# W602A.net
KiCad netlist of a schematic drawn in EAGLE
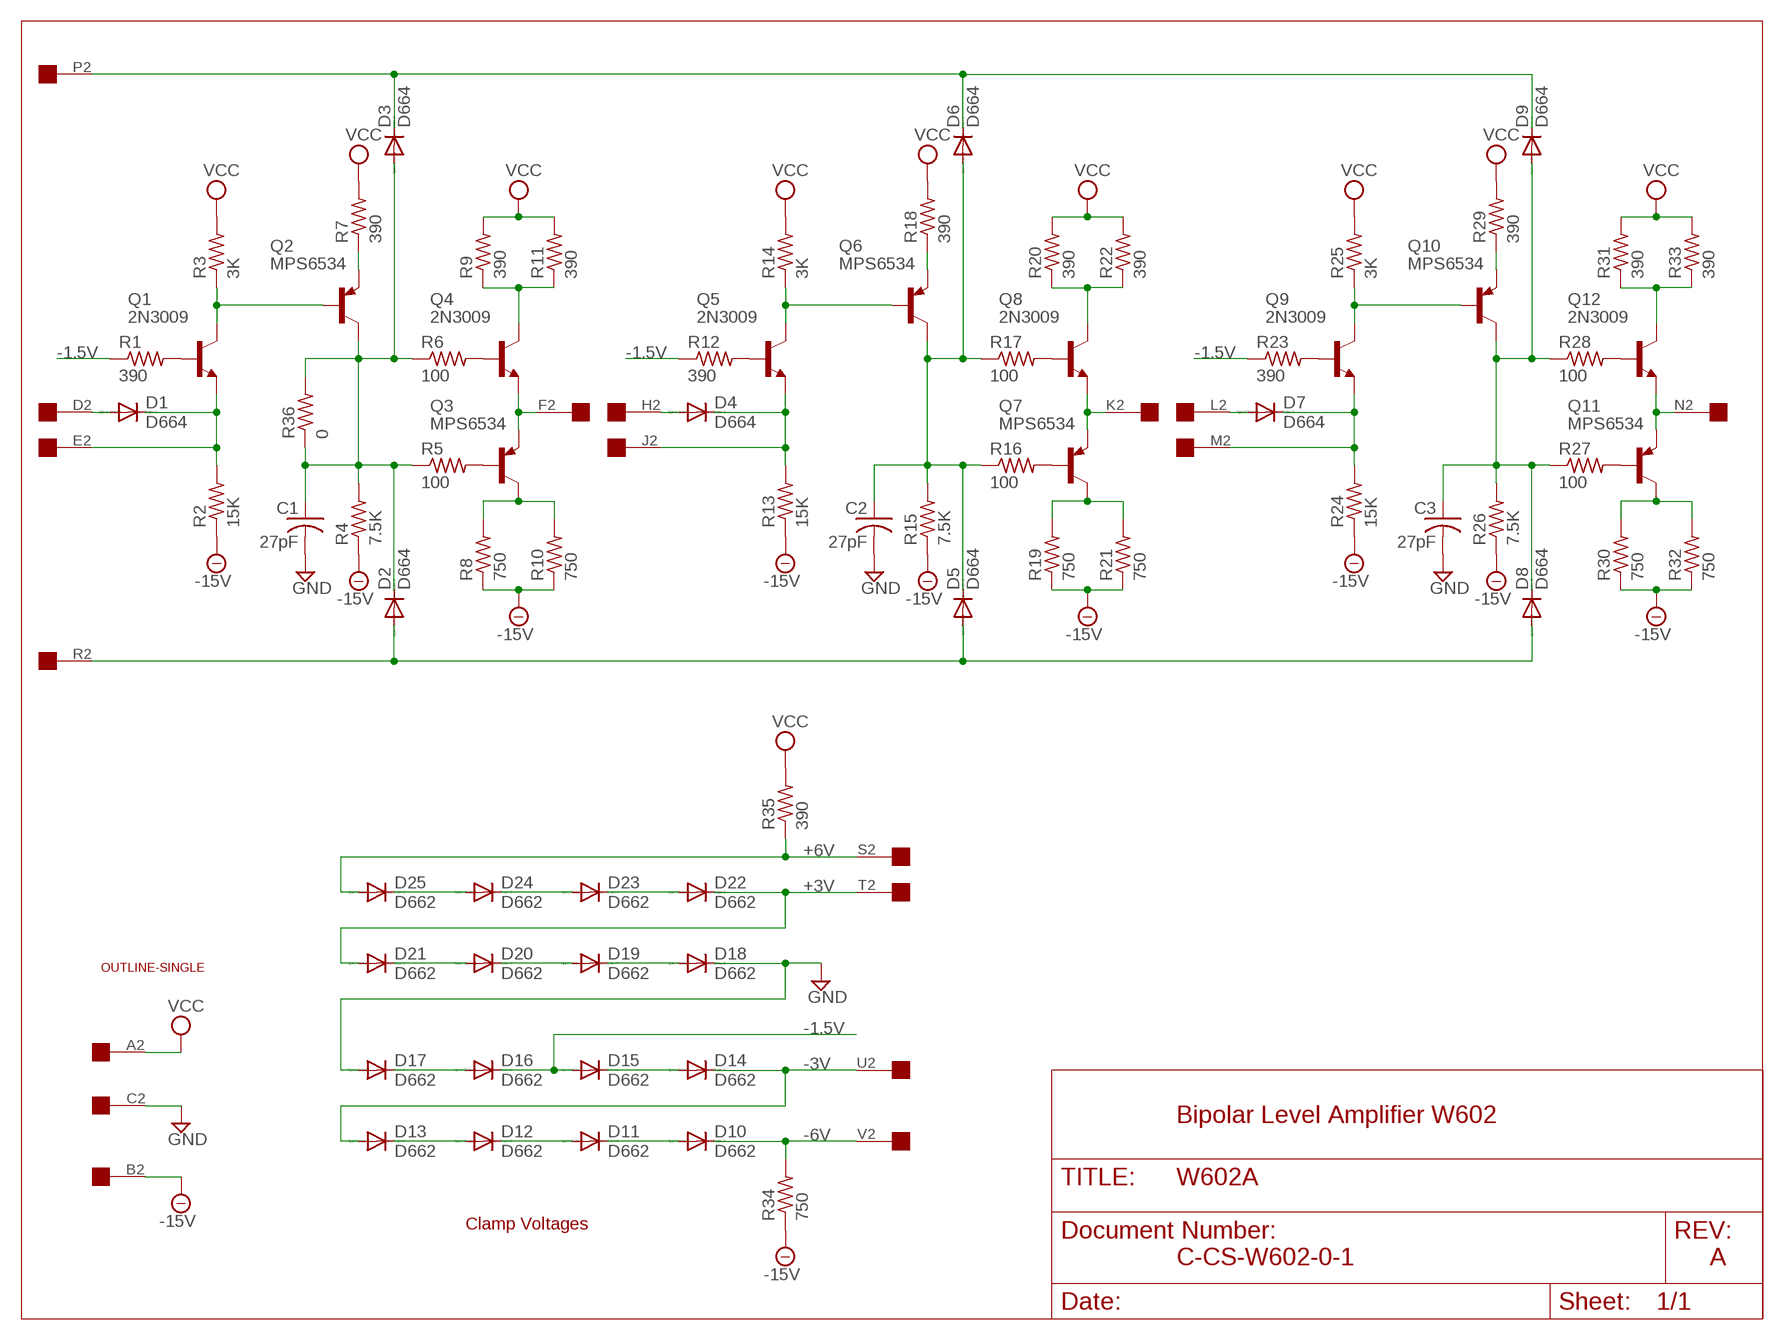
[diagram p0: schematic, sheet 1]

(export (version "E")
  (design (tool "Eeschema 10.0.6"))
  (components
    (comp (ref "C1")
      (value "27pF")
      (footprint "eagle-import:C063-025X075")
      (libsource (lib "eagle-import") (part "C-US"))
    )
    (comp (ref "C2")
      (value "27pF")
      (footprint "eagle-import:C063-025X075")
      (libsource (lib "eagle-import") (part "C-US"))
    )
    (comp (ref "C3")
      (value "27pF")
      (footprint "eagle-import:C063-025X075")
      (libsource (lib "eagle-import") (part "C-US"))
    )
    (comp (ref "D1")
      (value "D664")
      (footprint "eagle-import:DO35-10")
      (libsource (lib "eagle-import") (part "DIODE-DO35-10"))
    )
    (comp (ref "D2")
      (value "D664")
      (footprint "eagle-import:DO35-10")
      (libsource (lib "eagle-import") (part "DIODE-DO35-10"))
    )
    (comp (ref "D3")
      (value "D664")
      (footprint "eagle-import:DO35-10")
      (libsource (lib "eagle-import") (part "DIODE-DO35-10"))
    )
    (comp (ref "D4")
      (value "D664")
      (footprint "eagle-import:DO35-10")
      (libsource (lib "eagle-import") (part "DIODE-DO35-10"))
    )
    (comp (ref "D5")
      (value "D664")
      (footprint "eagle-import:DO35-10")
      (libsource (lib "eagle-import") (part "DIODE-DO35-10"))
    )
    (comp (ref "D6")
      (value "D664")
      (footprint "eagle-import:DO35-10")
      (libsource (lib "eagle-import") (part "DIODE-DO35-10"))
    )
    (comp (ref "D7")
      (value "D664")
      (footprint "eagle-import:DO35-10")
      (libsource (lib "eagle-import") (part "DIODE-DO35-10"))
    )
    (comp (ref "D8")
      (value "D664")
      (footprint "eagle-import:DO35-10")
      (libsource (lib "eagle-import") (part "DIODE-DO35-10"))
    )
    (comp (ref "D9")
      (value "D664")
      (footprint "eagle-import:DO35-10")
      (libsource (lib "eagle-import") (part "DIODE-DO35-10"))
    )
    (comp (ref "D10")
      (value "D662")
      (footprint "eagle-import:DO35-10")
      (libsource (lib "eagle-import") (part "DIODE-DO35-10"))
    )
    (comp (ref "D11")
      (value "D662")
      (footprint "eagle-import:DO35-10")
      (libsource (lib "eagle-import") (part "DIODE-DO35-10"))
    )
    (comp (ref "D12")
      (value "D662")
      (footprint "eagle-import:DO35-10")
      (libsource (lib "eagle-import") (part "DIODE-DO35-10"))
    )
    (comp (ref "D13")
      (value "D662")
      (footprint "eagle-import:DO35-10")
      (libsource (lib "eagle-import") (part "DIODE-DO35-10"))
    )
    (comp (ref "D14")
      (value "D662")
      (footprint "eagle-import:DO35-10")
      (libsource (lib "eagle-import") (part "DIODE-DO35-10"))
    )
    (comp (ref "D15")
      (value "D662")
      (footprint "eagle-import:DO35-10")
      (libsource (lib "eagle-import") (part "DIODE-DO35-10"))
    )
    (comp (ref "D16")
      (value "D662")
      (footprint "eagle-import:DO35-10")
      (libsource (lib "eagle-import") (part "DIODE-DO35-10"))
    )
    (comp (ref "D17")
      (value "D662")
      (footprint "eagle-import:DO35-10")
      (libsource (lib "eagle-import") (part "DIODE-DO35-10"))
    )
    (comp (ref "D18")
      (value "D662")
      (footprint "eagle-import:DO35-10")
      (libsource (lib "eagle-import") (part "DIODE-DO35-10"))
    )
    (comp (ref "D19")
      (value "D662")
      (footprint "eagle-import:DO35-10")
      (libsource (lib "eagle-import") (part "DIODE-DO35-10"))
    )
    (comp (ref "D20")
      (value "D662")
      (footprint "eagle-import:DO35-10")
      (libsource (lib "eagle-import") (part "DIODE-DO35-10"))
    )
    (comp (ref "D21")
      (value "D662")
      (footprint "eagle-import:DO35-10")
      (libsource (lib "eagle-import") (part "DIODE-DO35-10"))
    )
    (comp (ref "D22")
      (value "D662")
      (footprint "eagle-import:DO35-10")
      (libsource (lib "eagle-import") (part "DIODE-DO35-10"))
    )
    (comp (ref "D23")
      (value "D662")
      (footprint "eagle-import:DO35-10")
      (libsource (lib "eagle-import") (part "DIODE-DO35-10"))
    )
    (comp (ref "D24")
      (value "D662")
      (footprint "eagle-import:DO35-10")
      (libsource (lib "eagle-import") (part "DIODE-DO35-10"))
    )
    (comp (ref "D25")
      (value "D662")
      (footprint "eagle-import:DO35-10")
      (libsource (lib "eagle-import") (part "DIODE-DO35-10"))
    )
    (comp (ref "Q1")
      (value "2N3009")
      (footprint "eagle-import:TO5")
      (libsource (lib "eagle-import") (part "-NPN-TO5"))
    )
    (comp (ref "Q2")
      (value "MPS6534")
      (footprint "eagle-import:TO5")
      (libsource (lib "eagle-import") (part "-PNP-TO5"))
    )
    (comp (ref "Q3")
      (value "MPS6534")
      (footprint "eagle-import:TO5")
      (libsource (lib "eagle-import") (part "-PNP-TO5"))
    )
    (comp (ref "Q4")
      (value "2N3009")
      (footprint "eagle-import:TO5")
      (libsource (lib "eagle-import") (part "-NPN-TO5"))
    )
    (comp (ref "Q5")
      (value "2N3009")
      (footprint "eagle-import:TO5")
      (libsource (lib "eagle-import") (part "-NPN-TO5"))
    )
    (comp (ref "Q6")
      (value "MPS6534")
      (footprint "eagle-import:TO5")
      (libsource (lib "eagle-import") (part "-PNP-TO5"))
    )
    (comp (ref "Q7")
      (value "MPS6534")
      (footprint "eagle-import:TO5")
      (libsource (lib "eagle-import") (part "-PNP-TO5"))
    )
    (comp (ref "Q8")
      (value "2N3009")
      (footprint "eagle-import:TO5")
      (libsource (lib "eagle-import") (part "-NPN-TO5"))
    )
    (comp (ref "Q9")
      (value "2N3009")
      (footprint "eagle-import:TO5")
      (libsource (lib "eagle-import") (part "-NPN-TO5"))
    )
    (comp (ref "Q10")
      (value "MPS6534")
      (footprint "eagle-import:TO5")
      (libsource (lib "eagle-import") (part "-PNP-TO5"))
    )
    (comp (ref "Q11")
      (value "MPS6534")
      (footprint "eagle-import:TO5")
      (libsource (lib "eagle-import") (part "-PNP-TO5"))
    )
    (comp (ref "Q12")
      (value "2N3009")
      (footprint "eagle-import:TO5")
      (libsource (lib "eagle-import") (part "-NPN-TO5"))
    )
    (comp (ref "R1")
      (value "390")
      (footprint "eagle-import:0207_10")
      (libsource (lib "eagle-import") (part "R-US_0207/10"))
    )
    (comp (ref "R2")
      (value "15K")
      (footprint "eagle-import:0207_10")
      (libsource (lib "eagle-import") (part "R-US_0207/10"))
    )
    (comp (ref "R3")
      (value "3K")
      (footprint "eagle-import:0207_10")
      (libsource (lib "eagle-import") (part "R-US_0207/10"))
    )
    (comp (ref "R4")
      (value "7.5K")
      (footprint "eagle-import:0207_10")
      (libsource (lib "eagle-import") (part "R-US_0207/10"))
    )
    (comp (ref "R5")
      (value "100")
      (footprint "eagle-import:0207_10")
      (libsource (lib "eagle-import") (part "R-US_0207/10"))
    )
    (comp (ref "R6")
      (value "100")
      (footprint "eagle-import:0207_10")
      (libsource (lib "eagle-import") (part "R-US_0207/10"))
    )
    (comp (ref "R7")
      (value "390")
      (footprint "eagle-import:0207_10")
      (libsource (lib "eagle-import") (part "R-US_0207/10"))
    )
    (comp (ref "R8")
      (value "750")
      (footprint "eagle-import:0207_10")
      (libsource (lib "eagle-import") (part "R-US_0207/10"))
    )
    (comp (ref "R9")
      (value "390")
      (footprint "eagle-import:0207_10")
      (libsource (lib "eagle-import") (part "R-US_0207/10"))
    )
    (comp (ref "R10")
      (value "750")
      (footprint "eagle-import:0207_10")
      (libsource (lib "eagle-import") (part "R-US_0207/10"))
    )
    (comp (ref "R11")
      (value "390")
      (footprint "eagle-import:0207_10")
      (libsource (lib "eagle-import") (part "R-US_0207/10"))
    )
    (comp (ref "R12")
      (value "390")
      (footprint "eagle-import:0207_10")
      (libsource (lib "eagle-import") (part "R-US_0207/10"))
    )
    (comp (ref "R13")
      (value "15K")
      (footprint "eagle-import:0207_10")
      (libsource (lib "eagle-import") (part "R-US_0207/10"))
    )
    (comp (ref "R14")
      (value "3K")
      (footprint "eagle-import:0207_10")
      (libsource (lib "eagle-import") (part "R-US_0207/10"))
    )
    (comp (ref "R15")
      (value "7.5K")
      (footprint "eagle-import:0207_10")
      (libsource (lib "eagle-import") (part "R-US_0207/10"))
    )
    (comp (ref "R16")
      (value "100")
      (footprint "eagle-import:0207_10")
      (libsource (lib "eagle-import") (part "R-US_0207/10"))
    )
    (comp (ref "R17")
      (value "100")
      (footprint "eagle-import:0207_10")
      (libsource (lib "eagle-import") (part "R-US_0207/10"))
    )
    (comp (ref "R18")
      (value "390")
      (footprint "eagle-import:0207_10")
      (libsource (lib "eagle-import") (part "R-US_0207/10"))
    )
    (comp (ref "R19")
      (value "750")
      (footprint "eagle-import:0207_10")
      (libsource (lib "eagle-import") (part "R-US_0207/10"))
    )
    (comp (ref "R20")
      (value "390")
      (footprint "eagle-import:0207_10")
      (libsource (lib "eagle-import") (part "R-US_0207/10"))
    )
    (comp (ref "R21")
      (value "750")
      (footprint "eagle-import:0207_10")
      (libsource (lib "eagle-import") (part "R-US_0207/10"))
    )
    (comp (ref "R22")
      (value "390")
      (footprint "eagle-import:0207_10")
      (libsource (lib "eagle-import") (part "R-US_0207/10"))
    )
    (comp (ref "R23")
      (value "390")
      (footprint "eagle-import:0207_10")
      (libsource (lib "eagle-import") (part "R-US_0207/10"))
    )
    (comp (ref "R24")
      (value "15K")
      (footprint "eagle-import:0207_10")
      (libsource (lib "eagle-import") (part "R-US_0207/10"))
    )
    (comp (ref "R25")
      (value "3K")
      (footprint "eagle-import:0207_10")
      (libsource (lib "eagle-import") (part "R-US_0207/10"))
    )
    (comp (ref "R26")
      (value "7.5K")
      (footprint "eagle-import:0207_10")
      (libsource (lib "eagle-import") (part "R-US_0207/10"))
    )
    (comp (ref "R27")
      (value "100")
      (footprint "eagle-import:0207_10")
      (libsource (lib "eagle-import") (part "R-US_0207/10"))
    )
    (comp (ref "R28")
      (value "100")
      (footprint "eagle-import:0207_10")
      (libsource (lib "eagle-import") (part "R-US_0207/10"))
    )
    (comp (ref "R29")
      (value "390")
      (footprint "eagle-import:0207_10")
      (libsource (lib "eagle-import") (part "R-US_0207/10"))
    )
    (comp (ref "R30")
      (value "750")
      (footprint "eagle-import:0207_10")
      (libsource (lib "eagle-import") (part "R-US_0207/10"))
    )
    (comp (ref "R31")
      (value "390")
      (footprint "eagle-import:0207_10")
      (libsource (lib "eagle-import") (part "R-US_0207/10"))
    )
    (comp (ref "R32")
      (value "750")
      (footprint "eagle-import:0207_10")
      (libsource (lib "eagle-import") (part "R-US_0207/10"))
    )
    (comp (ref "R33")
      (value "390")
      (footprint "eagle-import:0207_10")
      (libsource (lib "eagle-import") (part "R-US_0207/10"))
    )
    (comp (ref "R34")
      (value "750")
      (footprint "eagle-import:0207_10")
      (libsource (lib "eagle-import") (part "R-US_0207/10"))
    )
    (comp (ref "R35")
      (value "390")
      (footprint "eagle-import:0207_10")
      (libsource (lib "eagle-import") (part "R-US_0207/10"))
    )
    (comp (ref "R36")
      (value "0")
      (footprint "eagle-import:0207_10")
      (libsource (lib "eagle-import") (part "R-US_0207/10"))
    )
    (comp (ref "U$1")
      (value "OUTLINE-SINGLE")
      (footprint "eagle-import:SINGLE")
      (libsource (lib "eagle-import") (part "OUTLINE-SINGLE"))
    )
    (comp (ref "U$2")
      (value "EDGE-1")
      (footprint "eagle-import:EDGE-CON1")
      (libsource (lib "eagle-import") (part "EDGE-1"))
    )
  )
  (nets
    (net (code "1") (name "-15V") (class "Default")
      (node (ref "R10") (pin "1") (pinfunction "1_1") (pintype "passive"))
      (node (ref "R13") (pin "1") (pinfunction "1_1") (pintype "passive"))
      (node (ref "R15") (pin "1") (pinfunction "1_1") (pintype "passive"))
      (node (ref "R19") (pin "1") (pinfunction "1_1") (pintype "passive"))
      (node (ref "R2") (pin "1") (pinfunction "1_1") (pintype "passive"))
      (node (ref "R21") (pin "1") (pinfunction "1_1") (pintype "passive"))
      (node (ref "R24") (pin "1") (pinfunction "1_1") (pintype "passive"))
      (node (ref "R26") (pin "1") (pinfunction "1_1") (pintype "passive"))
      (node (ref "R30") (pin "1") (pinfunction "1_1") (pintype "passive"))
      (node (ref "R32") (pin "1") (pinfunction "1_1") (pintype "passive"))
      (node (ref "R34") (pin "1") (pinfunction "1_1") (pintype "passive"))
      (node (ref "R4") (pin "1") (pinfunction "1_1") (pintype "passive"))
      (node (ref "R8") (pin "1") (pinfunction "1_1") (pintype "passive"))
      (node (ref "U$2") (pin "B2") (pinfunction "1_B2") (pintype "bidirectional"))
    )
    (net (code "2") (name "/+3V") (class "Default")
      (node (ref "D21") (pin "A") (pinfunction "A_A") (pintype "passive"))
      (node (ref "D22") (pin "C") (pinfunction "C_C") (pintype "passive"))
      (node (ref "U$2") (pin "T2") (pinfunction "1_T2") (pintype "bidirectional"))
    )
    (net (code "3") (name "/+6V") (class "Default")
      (node (ref "D25") (pin "A") (pinfunction "A_A") (pintype "passive"))
      (node (ref "R35") (pin "1") (pinfunction "1_1") (pintype "passive"))
      (node (ref "U$2") (pin "S2") (pinfunction "1_S2") (pintype "bidirectional"))
    )
    (net (code "4") (name "/-1.5V") (class "Default")
      (node (ref "D15") (pin "A") (pinfunction "A_A") (pintype "passive"))
      (node (ref "D16") (pin "C") (pinfunction "C_C") (pintype "passive"))
      (node (ref "R1") (pin "1") (pinfunction "1_1") (pintype "passive"))
      (node (ref "R12") (pin "1") (pinfunction "1_1") (pintype "passive"))
      (node (ref "R23") (pin "1") (pinfunction "1_1") (pintype "passive"))
    )
    (net (code "5") (name "/-3V") (class "Default")
      (node (ref "D13") (pin "A") (pinfunction "A_A") (pintype "passive"))
      (node (ref "D14") (pin "C") (pinfunction "C_C") (pintype "passive"))
      (node (ref "U$2") (pin "U2") (pinfunction "1_U2") (pintype "bidirectional"))
    )
    (net (code "6") (name "/-6V") (class "Default")
      (node (ref "D10") (pin "C") (pinfunction "C_C") (pintype "passive"))
      (node (ref "R34") (pin "2") (pinfunction "2_2") (pintype "passive"))
      (node (ref "U$2") (pin "V2") (pinfunction "1_V2") (pintype "bidirectional"))
    )
    (net (code "7") (name "GND") (class "Default")
      (node (ref "C1") (pin "2") (pinfunction "2_2") (pintype "passive"))
      (node (ref "C2") (pin "2") (pinfunction "2_2") (pintype "passive"))
      (node (ref "C3") (pin "2") (pinfunction "2_2") (pintype "passive"))
      (node (ref "D17") (pin "A") (pinfunction "A_A") (pintype "passive"))
      (node (ref "D18") (pin "C") (pinfunction "C_C") (pintype "passive"))
      (node (ref "U$2") (pin "C2") (pinfunction "1_C2") (pintype "bidirectional"))
    )
    (net (code "8") (name "Net-(D10-PadA)") (class "Default")
      (node (ref "D10") (pin "A") (pinfunction "A_A") (pintype "passive"))
      (node (ref "D11") (pin "C") (pinfunction "C_C") (pintype "passive"))
    )
    (net (code "9") (name "Net-(D11-PadA)") (class "Default")
      (node (ref "D11") (pin "A") (pinfunction "A_A") (pintype "passive"))
      (node (ref "D12") (pin "C") (pinfunction "C_C") (pintype "passive"))
    )
    (net (code "10") (name "Net-(D12-PadA)") (class "Default")
      (node (ref "D12") (pin "A") (pinfunction "A_A") (pintype "passive"))
      (node (ref "D13") (pin "C") (pinfunction "C_C") (pintype "passive"))
    )
    (net (code "11") (name "Net-(D14-PadA)") (class "Default")
      (node (ref "D14") (pin "A") (pinfunction "A_A") (pintype "passive"))
      (node (ref "D15") (pin "C") (pinfunction "C_C") (pintype "passive"))
    )
    (net (code "12") (name "Net-(D16-PadA)") (class "Default")
      (node (ref "D16") (pin "A") (pinfunction "A_A") (pintype "passive"))
      (node (ref "D17") (pin "C") (pinfunction "C_C") (pintype "passive"))
    )
    (net (code "13") (name "Net-(D18-PadA)") (class "Default")
      (node (ref "D18") (pin "A") (pinfunction "A_A") (pintype "passive"))
      (node (ref "D19") (pin "C") (pinfunction "C_C") (pintype "passive"))
    )
    (net (code "14") (name "Net-(D19-PadA)") (class "Default")
      (node (ref "D19") (pin "A") (pinfunction "A_A") (pintype "passive"))
      (node (ref "D20") (pin "C") (pinfunction "C_C") (pintype "passive"))
    )
    (net (code "15") (name "Net-(D20-PadA)") (class "Default")
      (node (ref "D20") (pin "A") (pinfunction "A_A") (pintype "passive"))
      (node (ref "D21") (pin "C") (pinfunction "C_C") (pintype "passive"))
    )
    (net (code "16") (name "Net-(D22-PadA)") (class "Default")
      (node (ref "D22") (pin "A") (pinfunction "A_A") (pintype "passive"))
      (node (ref "D23") (pin "C") (pinfunction "C_C") (pintype "passive"))
    )
    (net (code "17") (name "Net-(D23-PadA)") (class "Default")
      (node (ref "D23") (pin "A") (pinfunction "A_A") (pintype "passive"))
      (node (ref "D24") (pin "C") (pinfunction "C_C") (pintype "passive"))
    )
    (net (code "18") (name "Net-(D24-PadA)") (class "Default")
      (node (ref "D24") (pin "A") (pinfunction "A_A") (pintype "passive"))
      (node (ref "D25") (pin "C") (pinfunction "C_C") (pintype "passive"))
    )
    (net (code "19") (name "Net-(Q1-B)") (class "Default")
      (node (ref "Q1") (pin "2") (pinfunction "B_2") (pintype "passive"))
      (node (ref "R1") (pin "2") (pinfunction "2_2") (pintype "passive"))
    )
    (net (code "20") (name "Net-(Q1-C)") (class "Default")
      (node (ref "Q1") (pin "3") (pinfunction "C_3") (pintype "passive"))
      (node (ref "Q2") (pin "2") (pinfunction "B_2") (pintype "passive"))
      (node (ref "R3") (pin "1") (pinfunction "1_1") (pintype "passive"))
    )
    (net (code "21") (name "Net-(Q1-E)") (class "Default")
      (node (ref "D1") (pin "C") (pinfunction "C_C") (pintype "passive"))
      (node (ref "Q1") (pin "1") (pinfunction "E_1") (pintype "passive"))
      (node (ref "R2") (pin "2") (pinfunction "2_2") (pintype "passive"))
      (node (ref "U$2") (pin "E2") (pinfunction "1_E2") (pintype "bidirectional"))
    )
    (net (code "22") (name "Net-(Q2-C)") (class "Default")
      (node (ref "C1") (pin "1") (pinfunction "1_1") (pintype "passive"))
      (node (ref "D2") (pin "C") (pinfunction "C_C") (pintype "passive"))
      (node (ref "D3") (pin "A") (pinfunction "A_A") (pintype "passive"))
      (node (ref "Q2") (pin "3") (pinfunction "C_3") (pintype "passive"))
      (node (ref "R36") (pin "1") (pinfunction "1_1") (pintype "passive"))
      (node (ref "R36") (pin "2") (pinfunction "2_2") (pintype "passive"))
      (node (ref "R4") (pin "2") (pinfunction "2_2") (pintype "passive"))
      (node (ref "R5") (pin "1") (pinfunction "1_1") (pintype "passive"))
      (node (ref "R6") (pin "1") (pinfunction "1_1") (pintype "passive"))
    )
    (net (code "23") (name "Net-(Q2-E)") (class "Default")
      (node (ref "Q2") (pin "1") (pinfunction "E_1") (pintype "passive"))
      (node (ref "R7") (pin "1") (pinfunction "1_1") (pintype "passive"))
    )
    (net (code "24") (name "Net-(Q3-B)") (class "Default")
      (node (ref "Q3") (pin "2") (pinfunction "B_2") (pintype "passive"))
      (node (ref "R5") (pin "2") (pinfunction "2_2") (pintype "passive"))
    )
    (net (code "25") (name "Net-(Q3-C)") (class "Default")
      (node (ref "Q3") (pin "3") (pinfunction "C_3") (pintype "passive"))
      (node (ref "R10") (pin "2") (pinfunction "2_2") (pintype "passive"))
      (node (ref "R8") (pin "2") (pinfunction "2_2") (pintype "passive"))
    )
    (net (code "26") (name "Net-(Q3-E)") (class "Default")
      (node (ref "Q3") (pin "1") (pinfunction "E_1") (pintype "passive"))
      (node (ref "Q4") (pin "1") (pinfunction "E_1") (pintype "passive"))
      (node (ref "U$2") (pin "F2") (pinfunction "1_F2") (pintype "bidirectional"))
    )
    (net (code "27") (name "Net-(Q4-B)") (class "Default")
      (node (ref "Q4") (pin "2") (pinfunction "B_2") (pintype "passive"))
      (node (ref "R6") (pin "2") (pinfunction "2_2") (pintype "passive"))
    )
    (net (code "28") (name "Net-(Q4-C)") (class "Default")
      (node (ref "Q4") (pin "3") (pinfunction "C_3") (pintype "passive"))
      (node (ref "R11") (pin "1") (pinfunction "1_1") (pintype "passive"))
      (node (ref "R9") (pin "1") (pinfunction "1_1") (pintype "passive"))
    )
    (net (code "29") (name "Net-(Q5-B)") (class "Default")
      (node (ref "Q5") (pin "2") (pinfunction "B_2") (pintype "passive"))
      (node (ref "R12") (pin "2") (pinfunction "2_2") (pintype "passive"))
    )
    (net (code "30") (name "Net-(Q5-C)") (class "Default")
      (node (ref "Q5") (pin "3") (pinfunction "C_3") (pintype "passive"))
      (node (ref "Q6") (pin "2") (pinfunction "B_2") (pintype "passive"))
      (node (ref "R14") (pin "1") (pinfunction "1_1") (pintype "passive"))
    )
    (net (code "31") (name "Net-(Q5-E)") (class "Default")
      (node (ref "D4") (pin "C") (pinfunction "C_C") (pintype "passive"))
      (node (ref "Q5") (pin "1") (pinfunction "E_1") (pintype "passive"))
      (node (ref "R13") (pin "2") (pinfunction "2_2") (pintype "passive"))
      (node (ref "U$2") (pin "J2") (pinfunction "1_J2") (pintype "bidirectional"))
    )
    (net (code "32") (name "Net-(Q6-C)") (class "Default")
      (node (ref "C2") (pin "1") (pinfunction "1_1") (pintype "passive"))
      (node (ref "D5") (pin "C") (pinfunction "C_C") (pintype "passive"))
      (node (ref "D6") (pin "A") (pinfunction "A_A") (pintype "passive"))
      (node (ref "Q6") (pin "3") (pinfunction "C_3") (pintype "passive"))
      (node (ref "R15") (pin "2") (pinfunction "2_2") (pintype "passive"))
      (node (ref "R16") (pin "1") (pinfunction "1_1") (pintype "passive"))
      (node (ref "R17") (pin "1") (pinfunction "1_1") (pintype "passive"))
    )
    (net (code "33") (name "Net-(Q6-E)") (class "Default")
      (node (ref "Q6") (pin "1") (pinfunction "E_1") (pintype "passive"))
      (node (ref "R18") (pin "1") (pinfunction "1_1") (pintype "passive"))
    )
    (net (code "34") (name "Net-(Q7-B)") (class "Default")
      (node (ref "Q7") (pin "2") (pinfunction "B_2") (pintype "passive"))
      (node (ref "R16") (pin "2") (pinfunction "2_2") (pintype "passive"))
    )
    (net (code "35") (name "Net-(Q7-C)") (class "Default")
      (node (ref "Q7") (pin "3") (pinfunction "C_3") (pintype "passive"))
      (node (ref "R19") (pin "2") (pinfunction "2_2") (pintype "passive"))
      (node (ref "R21") (pin "2") (pinfunction "2_2") (pintype "passive"))
    )
    (net (code "36") (name "Net-(Q7-E)") (class "Default")
      (node (ref "Q7") (pin "1") (pinfunction "E_1") (pintype "passive"))
      (node (ref "Q8") (pin "1") (pinfunction "E_1") (pintype "passive"))
      (node (ref "U$2") (pin "K2") (pinfunction "1_K2") (pintype "bidirectional"))
    )
    (net (code "37") (name "Net-(Q8-B)") (class "Default")
      (node (ref "Q8") (pin "2") (pinfunction "B_2") (pintype "passive"))
      (node (ref "R17") (pin "2") (pinfunction "2_2") (pintype "passive"))
    )
    (net (code "38") (name "Net-(Q8-C)") (class "Default")
      (node (ref "Q8") (pin "3") (pinfunction "C_3") (pintype "passive"))
      (node (ref "R20") (pin "1") (pinfunction "1_1") (pintype "passive"))
      (node (ref "R22") (pin "1") (pinfunction "1_1") (pintype "passive"))
    )
    (net (code "39") (name "Net-(Q9-B)") (class "Default")
      (node (ref "Q9") (pin "2") (pinfunction "B_2") (pintype "passive"))
      (node (ref "R23") (pin "2") (pinfunction "2_2") (pintype "passive"))
    )
    (net (code "40") (name "Net-(Q9-E)") (class "Default")
      (node (ref "D7") (pin "C") (pinfunction "C_C") (pintype "passive"))
      (node (ref "Q9") (pin "1") (pinfunction "E_1") (pintype "passive"))
      (node (ref "R24") (pin "2") (pinfunction "2_2") (pintype "passive"))
      (node (ref "U$2") (pin "M2") (pinfunction "1_M2") (pintype "bidirectional"))
    )
    (net (code "41") (name "Net-(Q10-B)") (class "Default")
      (node (ref "Q10") (pin "2") (pinfunction "B_2") (pintype "passive"))
      (node (ref "Q9") (pin "3") (pinfunction "C_3") (pintype "passive"))
      (node (ref "R25") (pin "1") (pinfunction "1_1") (pintype "passive"))
    )
    (net (code "42") (name "Net-(Q10-C)") (class "Default")
      (node (ref "C3") (pin "1") (pinfunction "1_1") (pintype "passive"))
      (node (ref "D8") (pin "C") (pinfunction "C_C") (pintype "passive"))
      (node (ref "D9") (pin "A") (pinfunction "A_A") (pintype "passive"))
      (node (ref "Q10") (pin "3") (pinfunction "C_3") (pintype "passive"))
      (node (ref "R26") (pin "2") (pinfunction "2_2") (pintype "passive"))
      (node (ref "R27") (pin "1") (pinfunction "1_1") (pintype "passive"))
      (node (ref "R28") (pin "1") (pinfunction "1_1") (pintype "passive"))
    )
    (net (code "43") (name "Net-(Q10-E)") (class "Default")
      (node (ref "Q10") (pin "1") (pinfunction "E_1") (pintype "passive"))
      (node (ref "R29") (pin "1") (pinfunction "1_1") (pintype "passive"))
    )
    (net (code "44") (name "Net-(Q11-B)") (class "Default")
      (node (ref "Q11") (pin "2") (pinfunction "B_2") (pintype "passive"))
      (node (ref "R27") (pin "2") (pinfunction "2_2") (pintype "passive"))
    )
    (net (code "45") (name "Net-(Q11-C)") (class "Default")
      (node (ref "Q11") (pin "3") (pinfunction "C_3") (pintype "passive"))
      (node (ref "R30") (pin "2") (pinfunction "2_2") (pintype "passive"))
      (node (ref "R32") (pin "2") (pinfunction "2_2") (pintype "passive"))
    )
    (net (code "46") (name "Net-(Q11-E)") (class "Default")
      (node (ref "Q11") (pin "1") (pinfunction "E_1") (pintype "passive"))
      (node (ref "Q12") (pin "1") (pinfunction "E_1") (pintype "passive"))
      (node (ref "U$2") (pin "N2") (pinfunction "1_N2") (pintype "bidirectional"))
    )
    (net (code "47") (name "Net-(Q12-B)") (class "Default")
      (node (ref "Q12") (pin "2") (pinfunction "B_2") (pintype "passive"))
      (node (ref "R28") (pin "2") (pinfunction "2_2") (pintype "passive"))
    )
    (net (code "48") (name "Net-(Q12-C)") (class "Default")
      (node (ref "Q12") (pin "3") (pinfunction "C_3") (pintype "passive"))
      (node (ref "R31") (pin "1") (pinfunction "1_1") (pintype "passive"))
      (node (ref "R33") (pin "1") (pinfunction "1_1") (pintype "passive"))
    )
    (net (code "49") (name "Net-(U$2D-1)") (class "Default")
      (node (ref "D1") (pin "A") (pinfunction "A_A") (pintype "passive"))
      (node (ref "U$2") (pin "D2") (pinfunction "1_D2") (pintype "bidirectional"))
    )
    (net (code "50") (name "Net-(U$2G-1)") (class "Default")
      (node (ref "D4") (pin "A") (pinfunction "A_A") (pintype "passive"))
      (node (ref "U$2") (pin "H2") (pinfunction "1_H2") (pintype "bidirectional"))
    )
    (net (code "51") (name "Net-(U$2J-1)") (class "Default")
      (node (ref "D7") (pin "A") (pinfunction "A_A") (pintype "passive"))
      (node (ref "U$2") (pin "L2") (pinfunction "1_L2") (pintype "bidirectional"))
    )
    (net (code "52") (name "Net-(U$2M-1)") (class "Default")
      (node (ref "D3") (pin "C") (pinfunction "C_C") (pintype "passive"))
      (node (ref "D6") (pin "C") (pinfunction "C_C") (pintype "passive"))
      (node (ref "D9") (pin "C") (pinfunction "C_C") (pintype "passive"))
      (node (ref "U$2") (pin "P2") (pinfunction "1_P2") (pintype "bidirectional"))
    )
    (net (code "53") (name "Net-(U$2N-1)") (class "Default")
      (node (ref "D2") (pin "A") (pinfunction "A_A") (pintype "passive"))
      (node (ref "D5") (pin "A") (pinfunction "A_A") (pintype "passive"))
      (node (ref "D8") (pin "A") (pinfunction "A_A") (pintype "passive"))
      (node (ref "U$2") (pin "R2") (pinfunction "1_R2") (pintype "bidirectional"))
    )
    (net (code "54") (name "VCC") (class "Default")
      (node (ref "R11") (pin "2") (pinfunction "2_2") (pintype "passive"))
      (node (ref "R14") (pin "2") (pinfunction "2_2") (pintype "passive"))
      (node (ref "R18") (pin "2") (pinfunction "2_2") (pintype "passive"))
      (node (ref "R20") (pin "2") (pinfunction "2_2") (pintype "passive"))
      (node (ref "R22") (pin "2") (pinfunction "2_2") (pintype "passive"))
      (node (ref "R25") (pin "2") (pinfunction "2_2") (pintype "passive"))
      (node (ref "R29") (pin "2") (pinfunction "2_2") (pintype "passive"))
      (node (ref "R3") (pin "2") (pinfunction "2_2") (pintype "passive"))
      (node (ref "R31") (pin "2") (pinfunction "2_2") (pintype "passive"))
      (node (ref "R33") (pin "2") (pinfunction "2_2") (pintype "passive"))
      (node (ref "R35") (pin "2") (pinfunction "2_2") (pintype "passive"))
      (node (ref "R7") (pin "2") (pinfunction "2_2") (pintype "passive"))
      (node (ref "R9") (pin "2") (pinfunction "2_2") (pintype "passive"))
      (node (ref "U$2") (pin "A2") (pinfunction "1_A2") (pintype "bidirectional"))
    )
  )
)
